# MCU063B_GPIO.net
KiCad netlist of a schematic drawn in Altium Designer
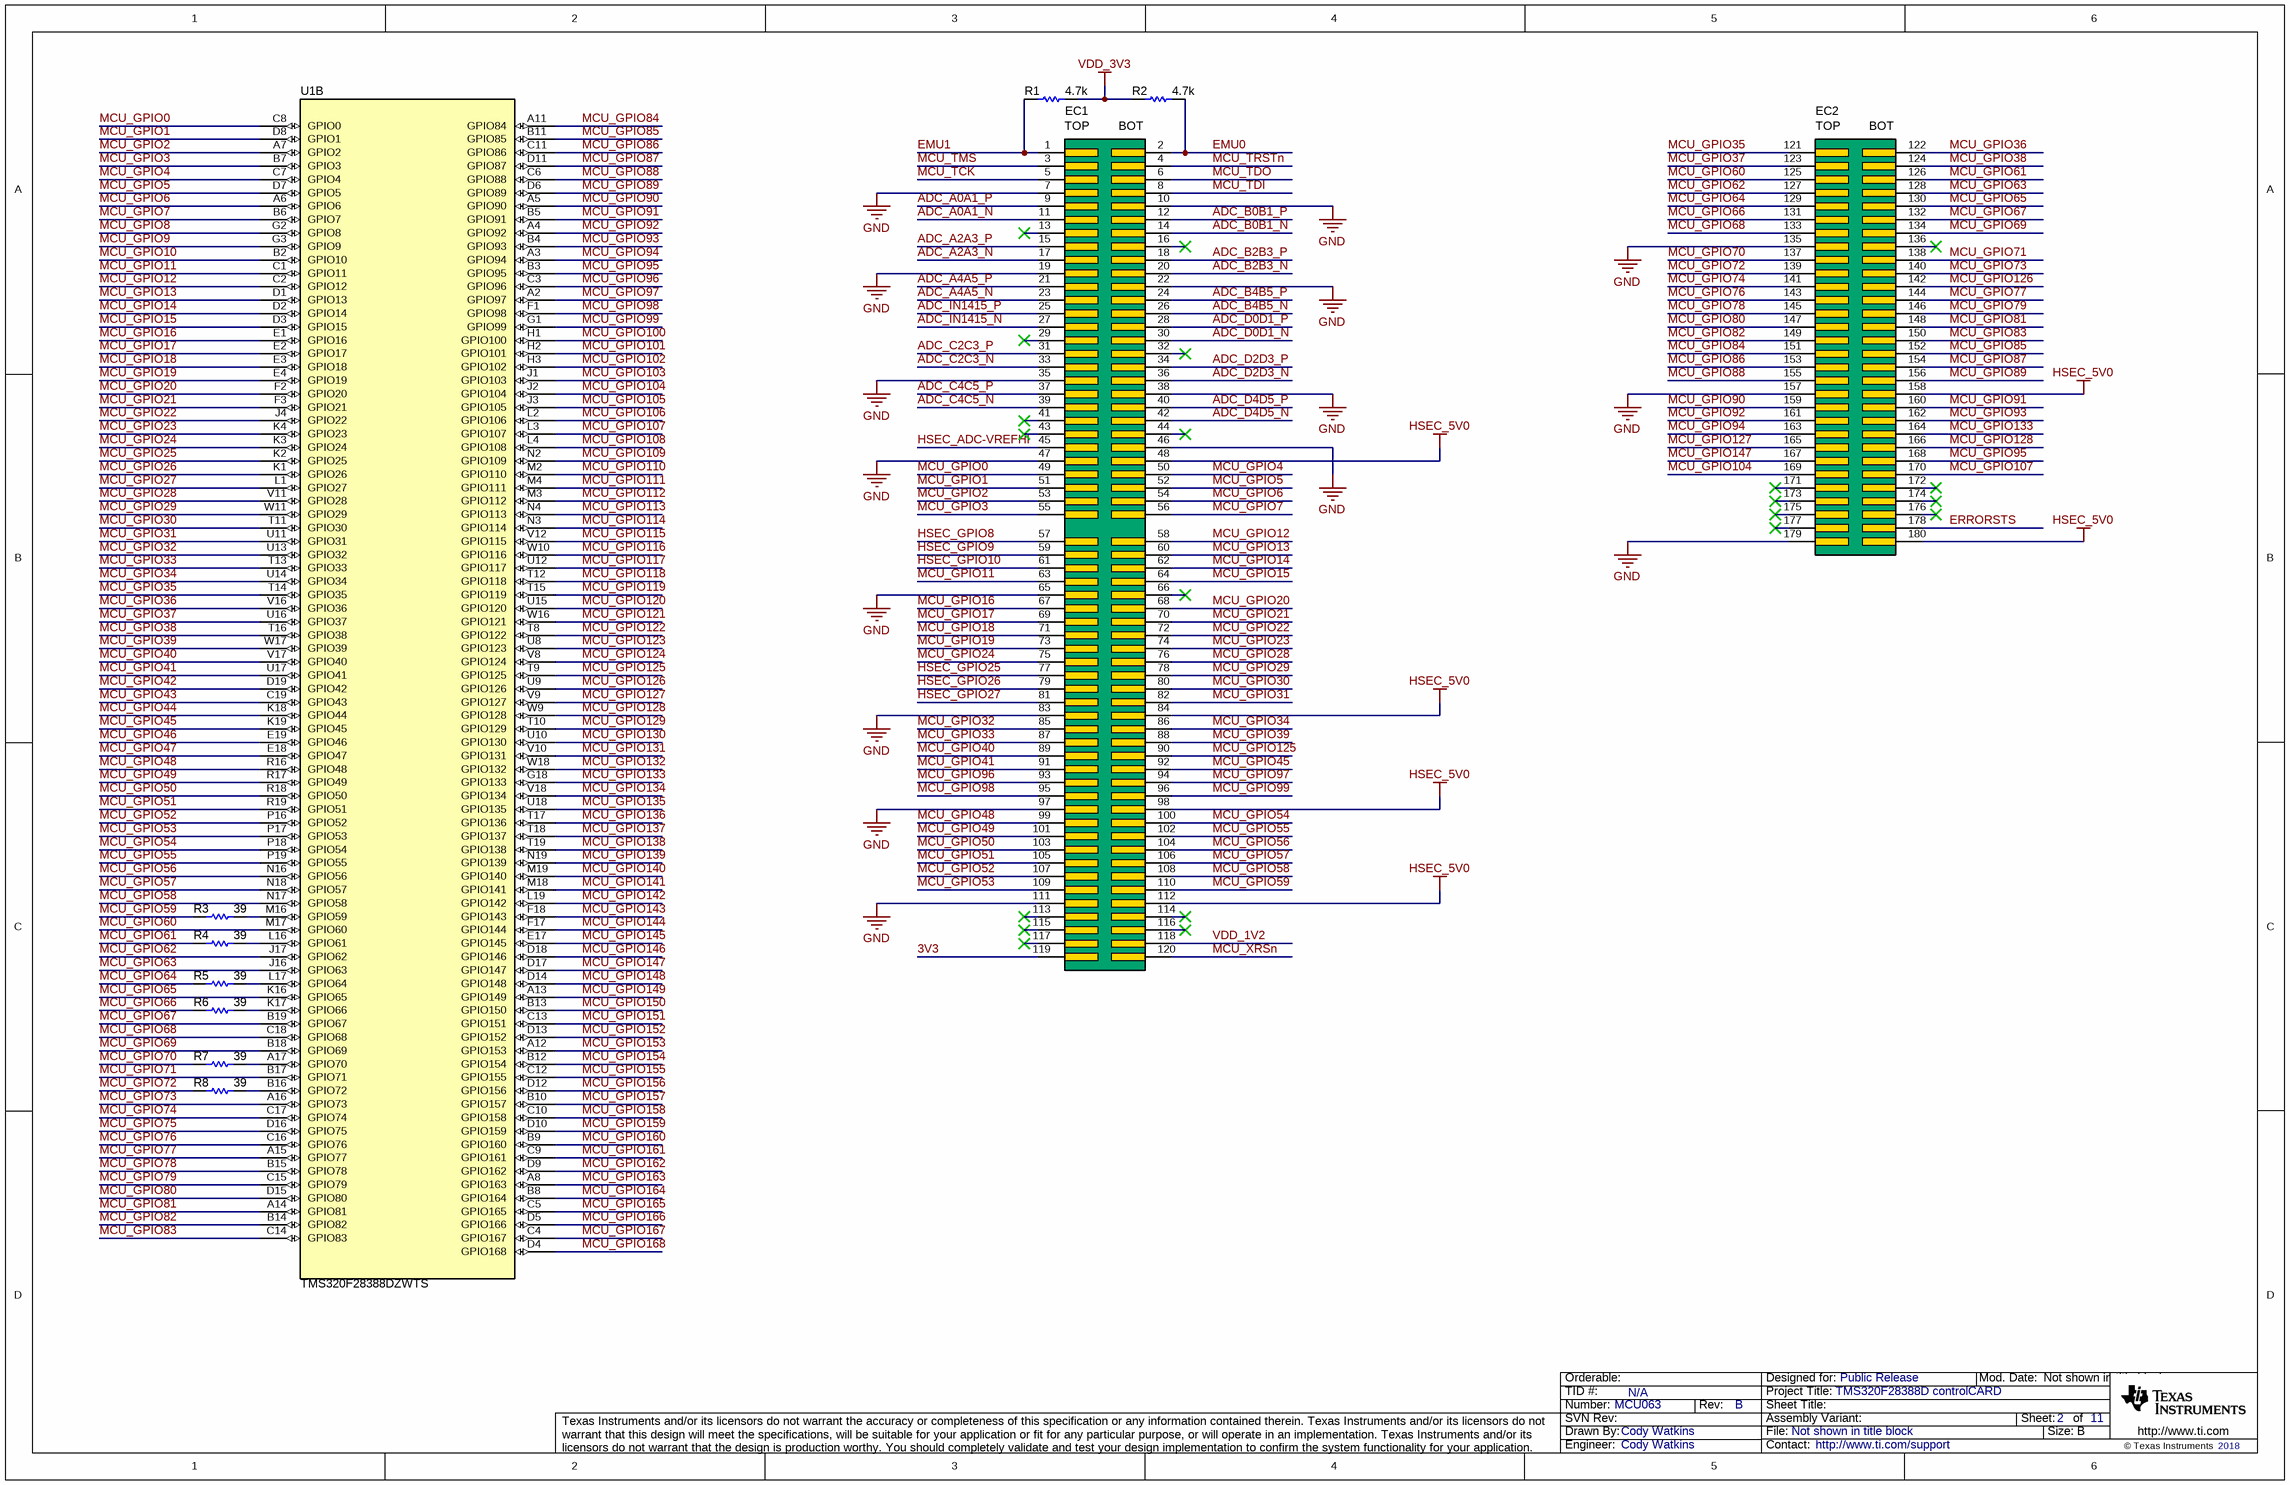
[diagram p0: MCU063B_GPIO.SchDoc]

(export (version "E")
  (design (tool "Eeschema 10.0.6"))
  (components
    (comp (ref "EC1")
      (value "controlCARD-120HSEC_Edge")
      (footprint "controlCARD-120HSEC_Edge")
      (description "C2000 controlCARD-120HSEC Edge Connector for Samtec HSEC8-160-01-L-DV-A-BL")
      (fields (field (name "MANUFACTURER") "Any"))
      (libsource (lib "Altium Vault - TI") (part "controlCARD-120HSEC_Edge"))
    )
    (comp (ref "EC2")
      (value "controlCARD-180HSEC-60pinAddon_Edge")
      (footprint "controlCARD-180HSEC-60pinAddon_Edge")
      (description "C2000 controlCARD-180HSEC (60-pin addon) Edge connector for Samtec HSEC8-130-01-L-DV-A")
      (fields (field (name "MANUFACTURER") "Any"))
      (libsource (lib "Altium Vault - TI") (part "controlCARD-180HSEC-60pinAddon_Edge"))
    )
    (comp (ref "R1")
      (value "CRCW04024K70JNED")
      (footprint "0402")
      (description "RES, 4.7 k, 5%, 0.063 W, AEC-Q200 Grade 0, 0402")
      (fields (field (name "MANUFACTURER") "Vishay-Dale") (field (name "VALUEDISPLAYED") "4.7k"))
      (libsource (lib "Altium Vault - TI") (part "Resistor"))
    )
    (comp (ref "R2")
      (value "CRCW04024K70JNED")
      (footprint "0402")
      (description "RES, 4.7 k, 5%, 0.063 W, AEC-Q200 Grade 0, 0402")
      (fields (field (name "MANUFACTURER") "Vishay-Dale") (field (name "VALUEDISPLAYED") "4.7k"))
      (libsource (lib "Altium Vault - TI") (part "Resistor"))
    )
    (comp (ref "R3")
      (value "CRCW040239R0JNED")
      (footprint "0402")
      (description "RES, 39, 5%, 0.063 W, AEC-Q200 Grade 0, 0402")
      (fields (field (name "MANUFACTURER") "Vishay-Dale") (field (name "VALUEDISPLAYED") "39"))
      (libsource (lib "Altium Vault - TI") (part "Resistor"))
    )
    (comp (ref "R4")
      (value "CRCW040239R0JNED")
      (footprint "0402")
      (description "RES, 39, 5%, 0.063 W, AEC-Q200 Grade 0, 0402")
      (fields (field (name "MANUFACTURER") "Vishay-Dale") (field (name "VALUEDISPLAYED") "39"))
      (libsource (lib "Altium Vault - TI") (part "Resistor"))
    )
    (comp (ref "R5")
      (value "CRCW040239R0JNED")
      (footprint "0402")
      (description "RES, 39, 5%, 0.063 W, AEC-Q200 Grade 0, 0402")
      (fields (field (name "MANUFACTURER") "Vishay-Dale") (field (name "VALUEDISPLAYED") "39"))
      (libsource (lib "Altium Vault - TI") (part "Resistor"))
    )
    (comp (ref "R6")
      (value "CRCW040239R0JNED")
      (footprint "0402")
      (description "RES, 39, 5%, 0.063 W, AEC-Q200 Grade 0, 0402")
      (fields (field (name "MANUFACTURER") "Vishay-Dale") (field (name "VALUEDISPLAYED") "39"))
      (libsource (lib "Altium Vault - TI") (part "Resistor"))
    )
    (comp (ref "R7")
      (value "CRCW040239R0JNED")
      (footprint "0402")
      (description "RES, 39, 5%, 0.063 W, AEC-Q200 Grade 0, 0402")
      (fields (field (name "MANUFACTURER") "Vishay-Dale") (field (name "VALUEDISPLAYED") "39"))
      (libsource (lib "Altium Vault - TI") (part "Resistor"))
    )
    (comp (ref "R8")
      (value "CRCW040239R0JNED")
      (footprint "0402")
      (description "RES, 39, 5%, 0.063 W, AEC-Q200 Grade 0, 0402")
      (fields (field (name "MANUFACTURER") "Vishay-Dale") (field (name "VALUEDISPLAYED") "39"))
      (libsource (lib "Altium Vault - TI") (part "Resistor"))
    )
    (comp (ref "U1")
      (value "TMS320F28388DZWTS")
      (footprint "ZWT0337A")
      (description "TMS320F28388DZWTS, ZWT0337A (NFBGA-337)")
      (fields
        (field (name "PARTNUMBER") "TMS320F28388DZWTS")
        (field (name "MANUFACTURER") "Texas Instruments")
      )
      (libsource (lib "Altium Vault - TI") (part "TMS320F28388"))
    )
  )
  (nets
    (net (code "1") (name "/3V3") (class "Default")
      (node (ref "EC1") (pin "119") (pinfunction "119_119") (pintype "passive"))
    )
    (net (code "2") (name "/ADC_A0A1_N") (class "Default")
      (node (ref "EC1") (pin "11") (pinfunction "11_11") (pintype "passive"))
    )
    (net (code "3") (name "/ADC_A0A1_P") (class "Default")
      (node (ref "EC1") (pin "9") (pinfunction "9_9") (pintype "passive"))
    )
    (net (code "4") (name "/ADC_A2A3_N") (class "Default")
      (node (ref "EC1") (pin "17") (pinfunction "17_17") (pintype "passive"))
    )
    (net (code "5") (name "/ADC_A2A3_P") (class "Default")
      (node (ref "EC1") (pin "15") (pinfunction "15_15") (pintype "passive"))
    )
    (net (code "6") (name "/ADC_A4A5_N") (class "Default")
      (node (ref "EC1") (pin "23") (pinfunction "23_23") (pintype "passive"))
    )
    (net (code "7") (name "/ADC_A4A5_P") (class "Default")
      (node (ref "EC1") (pin "21") (pinfunction "21_21") (pintype "passive"))
    )
    (net (code "8") (name "/ADC_B0B1_N") (class "Default")
      (node (ref "EC1") (pin "14") (pinfunction "14_14") (pintype "passive"))
    )
    (net (code "9") (name "/ADC_B0B1_P") (class "Default")
      (node (ref "EC1") (pin "12") (pinfunction "12_12") (pintype "passive"))
    )
    (net (code "10") (name "/ADC_B2B3_N") (class "Default")
      (node (ref "EC1") (pin "20") (pinfunction "20_20") (pintype "passive"))
    )
    (net (code "11") (name "/ADC_B2B3_P") (class "Default")
      (node (ref "EC1") (pin "18") (pinfunction "18_18") (pintype "passive"))
    )
    (net (code "12") (name "/ADC_B4B5_N") (class "Default")
      (node (ref "EC1") (pin "26") (pinfunction "26_26") (pintype "passive"))
    )
    (net (code "13") (name "/ADC_B4B5_P") (class "Default")
      (node (ref "EC1") (pin "24") (pinfunction "24_24") (pintype "passive"))
    )
    (net (code "14") (name "/ADC_C2C3_N") (class "Default")
      (node (ref "EC1") (pin "33") (pinfunction "33_33") (pintype "passive"))
    )
    (net (code "15") (name "/ADC_C2C3_P") (class "Default")
      (node (ref "EC1") (pin "31") (pinfunction "31_31") (pintype "passive"))
    )
    (net (code "16") (name "/ADC_C4C5_N") (class "Default")
      (node (ref "EC1") (pin "39") (pinfunction "39_39") (pintype "passive"))
    )
    (net (code "17") (name "/ADC_C4C5_P") (class "Default")
      (node (ref "EC1") (pin "37") (pinfunction "37_37") (pintype "passive"))
    )
    (net (code "18") (name "/ADC_D0D1_N") (class "Default")
      (node (ref "EC1") (pin "30") (pinfunction "30_30") (pintype "passive"))
    )
    (net (code "19") (name "/ADC_D0D1_P") (class "Default")
      (node (ref "EC1") (pin "28") (pinfunction "28_28") (pintype "passive"))
    )
    (net (code "20") (name "/ADC_D2D3_N") (class "Default")
      (node (ref "EC1") (pin "36") (pinfunction "36_36") (pintype "passive"))
    )
    (net (code "21") (name "/ADC_D2D3_P") (class "Default")
      (node (ref "EC1") (pin "34") (pinfunction "34_34") (pintype "passive"))
    )
    (net (code "22") (name "/ADC_D4D5_N") (class "Default")
      (node (ref "EC1") (pin "42") (pinfunction "42_42") (pintype "passive"))
    )
    (net (code "23") (name "/ADC_D4D5_P") (class "Default")
      (node (ref "EC1") (pin "40") (pinfunction "40_40") (pintype "passive"))
    )
    (net (code "24") (name "/ADC_IN1415_N") (class "Default")
      (node (ref "EC1") (pin "27") (pinfunction "27_27") (pintype "passive"))
    )
    (net (code "25") (name "/ADC_IN1415_P") (class "Default")
      (node (ref "EC1") (pin "25") (pinfunction "25_25") (pintype "passive"))
    )
    (net (code "26") (name "/EMU0") (class "Default")
      (node (ref "EC1") (pin "2") (pinfunction "2_2") (pintype "passive"))
      (node (ref "R2") (pin "2") (pinfunction "2_2") (pintype "passive"))
    )
    (net (code "27") (name "/EMU1") (class "Default")
      (node (ref "EC1") (pin "1") (pinfunction "1_1") (pintype "passive"))
      (node (ref "R1") (pin "1") (pinfunction "1_1") (pintype "passive"))
    )
    (net (code "28") (name "/ERRORSTS") (class "Default")
      (node (ref "EC2") (pin "178") (pinfunction "178_178") (pintype "passive"))
    )
    (net (code "29") (name "/HSEC_ADC-VREFHI") (class "Default")
      (node (ref "EC1") (pin "45") (pinfunction "45_45") (pintype "passive"))
    )
    (net (code "30") (name "/HSEC_GPIO8") (class "Default")
      (node (ref "EC1") (pin "57") (pinfunction "57_57") (pintype "passive"))
    )
    (net (code "31") (name "/HSEC_GPIO9") (class "Default")
      (node (ref "EC1") (pin "59") (pinfunction "59_59") (pintype "passive"))
    )
    (net (code "32") (name "/HSEC_GPIO10") (class "Default")
      (node (ref "EC1") (pin "61") (pinfunction "61_61") (pintype "passive"))
    )
    (net (code "33") (name "/HSEC_GPIO25") (class "Default")
      (node (ref "EC1") (pin "77") (pinfunction "77_77") (pintype "passive"))
    )
    (net (code "34") (name "/HSEC_GPIO26") (class "Default")
      (node (ref "EC1") (pin "79") (pinfunction "79_79") (pintype "passive"))
    )
    (net (code "35") (name "/HSEC_GPIO27") (class "Default")
      (node (ref "EC1") (pin "81") (pinfunction "81_81") (pintype "passive"))
    )
    (net (code "36") (name "/MCU_GPIO0") (class "Default")
      (node (ref "EC1") (pin "49") (pinfunction "49_49") (pintype "passive"))
      (node (ref "U1") (pin "C8") (pinfunction "GPIO0_C8") (pintype "bidirectional"))
    )
    (net (code "37") (name "/MCU_GPIO1") (class "Default")
      (node (ref "EC1") (pin "51") (pinfunction "51_51") (pintype "passive"))
      (node (ref "U1") (pin "D8") (pinfunction "GPIO1_D8") (pintype "bidirectional"))
    )
    (net (code "38") (name "/MCU_GPIO2") (class "Default")
      (node (ref "EC1") (pin "53") (pinfunction "53_53") (pintype "passive"))
      (node (ref "U1") (pin "A7") (pinfunction "GPIO2_A7") (pintype "bidirectional"))
    )
    (net (code "39") (name "/MCU_GPIO3") (class "Default")
      (node (ref "EC1") (pin "55") (pinfunction "55_55") (pintype "passive"))
      (node (ref "U1") (pin "B7") (pinfunction "GPIO3_B7") (pintype "bidirectional"))
    )
    (net (code "40") (name "/MCU_GPIO4") (class "Default")
      (node (ref "EC1") (pin "50") (pinfunction "50_50") (pintype "passive"))
      (node (ref "U1") (pin "C7") (pinfunction "GPIO4_C7") (pintype "bidirectional"))
    )
    (net (code "41") (name "/MCU_GPIO5") (class "Default")
      (node (ref "EC1") (pin "52") (pinfunction "52_52") (pintype "passive"))
      (node (ref "U1") (pin "D7") (pinfunction "GPIO5_D7") (pintype "bidirectional"))
    )
    (net (code "42") (name "/MCU_GPIO6") (class "Default")
      (node (ref "EC1") (pin "54") (pinfunction "54_54") (pintype "passive"))
      (node (ref "U1") (pin "A6") (pinfunction "GPIO6_A6") (pintype "bidirectional"))
    )
    (net (code "43") (name "/MCU_GPIO7") (class "Default")
      (node (ref "EC1") (pin "56") (pinfunction "56_56") (pintype "passive"))
      (node (ref "U1") (pin "B6") (pinfunction "GPIO7_B6") (pintype "bidirectional"))
    )
    (net (code "44") (name "/MCU_GPIO8") (class "Default")
      (node (ref "U1") (pin "G2") (pinfunction "GPIO8_G2") (pintype "bidirectional"))
    )
    (net (code "45") (name "/MCU_GPIO9") (class "Default")
      (node (ref "U1") (pin "G3") (pinfunction "GPIO9_G3") (pintype "bidirectional"))
    )
    (net (code "46") (name "/MCU_GPIO10") (class "Default")
      (node (ref "U1") (pin "B2") (pinfunction "GPIO10_B2") (pintype "bidirectional"))
    )
    (net (code "47") (name "/MCU_GPIO11") (class "Default")
      (node (ref "EC1") (pin "63") (pinfunction "63_63") (pintype "passive"))
      (node (ref "U1") (pin "C1") (pinfunction "GPIO11_C1") (pintype "bidirectional"))
    )
    (net (code "48") (name "/MCU_GPIO12") (class "Default")
      (node (ref "EC1") (pin "58") (pinfunction "58_58") (pintype "passive"))
      (node (ref "U1") (pin "C2") (pinfunction "GPIO12_C2") (pintype "bidirectional"))
    )
    (net (code "49") (name "/MCU_GPIO13") (class "Default")
      (node (ref "EC1") (pin "60") (pinfunction "60_60") (pintype "passive"))
      (node (ref "U1") (pin "D1") (pinfunction "GPIO13_D1") (pintype "bidirectional"))
    )
    (net (code "50") (name "/MCU_GPIO14") (class "Default")
      (node (ref "EC1") (pin "62") (pinfunction "62_62") (pintype "passive"))
      (node (ref "U1") (pin "D2") (pinfunction "GPIO14_D2") (pintype "bidirectional"))
    )
    (net (code "51") (name "/MCU_GPIO15") (class "Default")
      (node (ref "EC1") (pin "64") (pinfunction "64_64") (pintype "passive"))
      (node (ref "U1") (pin "D3") (pinfunction "GPIO15_D3") (pintype "bidirectional"))
    )
    (net (code "52") (name "/MCU_GPIO16") (class "Default")
      (node (ref "EC1") (pin "67") (pinfunction "67_67") (pintype "passive"))
      (node (ref "U1") (pin "E1") (pinfunction "GPIO16_E1") (pintype "bidirectional"))
    )
    (net (code "53") (name "/MCU_GPIO17") (class "Default")
      (node (ref "EC1") (pin "69") (pinfunction "69_69") (pintype "passive"))
      (node (ref "U1") (pin "E2") (pinfunction "GPIO17_E2") (pintype "bidirectional"))
    )
    (net (code "54") (name "/MCU_GPIO18") (class "Default")
      (node (ref "EC1") (pin "71") (pinfunction "71_71") (pintype "passive"))
      (node (ref "U1") (pin "E3") (pinfunction "GPIO18_E3") (pintype "bidirectional"))
    )
    (net (code "55") (name "/MCU_GPIO19") (class "Default")
      (node (ref "EC1") (pin "73") (pinfunction "73_73") (pintype "passive"))
      (node (ref "U1") (pin "E4") (pinfunction "GPIO19_E4") (pintype "bidirectional"))
    )
    (net (code "56") (name "/MCU_GPIO20") (class "Default")
      (node (ref "EC1") (pin "68") (pinfunction "68_68") (pintype "passive"))
      (node (ref "U1") (pin "F2") (pinfunction "GPIO20_F2") (pintype "bidirectional"))
    )
    (net (code "57") (name "/MCU_GPIO21") (class "Default")
      (node (ref "EC1") (pin "70") (pinfunction "70_70") (pintype "passive"))
      (node (ref "U1") (pin "F3") (pinfunction "GPIO21_F3") (pintype "bidirectional"))
    )
    (net (code "58") (name "/MCU_GPIO22") (class "Default")
      (node (ref "EC1") (pin "72") (pinfunction "72_72") (pintype "passive"))
      (node (ref "U1") (pin "J4") (pinfunction "GPIO22_J4") (pintype "bidirectional"))
    )
    (net (code "59") (name "/MCU_GPIO23") (class "Default")
      (node (ref "EC1") (pin "74") (pinfunction "74_74") (pintype "passive"))
      (node (ref "U1") (pin "K4") (pinfunction "GPIO23_K4") (pintype "bidirectional"))
    )
    (net (code "60") (name "/MCU_GPIO24") (class "Default")
      (node (ref "EC1") (pin "75") (pinfunction "75_75") (pintype "passive"))
      (node (ref "U1") (pin "K3") (pinfunction "GPIO24_K3") (pintype "bidirectional"))
    )
    (net (code "61") (name "/MCU_GPIO25") (class "Default")
      (node (ref "U1") (pin "K2") (pinfunction "GPIO25_K2") (pintype "bidirectional"))
    )
    (net (code "62") (name "/MCU_GPIO26") (class "Default")
      (node (ref "U1") (pin "K1") (pinfunction "GPIO26_K1") (pintype "bidirectional"))
    )
    (net (code "63") (name "/MCU_GPIO27") (class "Default")
      (node (ref "U1") (pin "L1") (pinfunction "GPIO27_L1") (pintype "bidirectional"))
    )
    (net (code "64") (name "/MCU_GPIO28") (class "Default")
      (node (ref "EC1") (pin "76") (pinfunction "76_76") (pintype "passive"))
      (node (ref "U1") (pin "V11") (pinfunction "GPIO28_V11") (pintype "bidirectional"))
    )
    (net (code "65") (name "/MCU_GPIO29") (class "Default")
      (node (ref "EC1") (pin "78") (pinfunction "78_78") (pintype "passive"))
      (node (ref "U1") (pin "W11") (pinfunction "GPIO29_W11") (pintype "bidirectional"))
    )
    (net (code "66") (name "/MCU_GPIO30") (class "Default")
      (node (ref "EC1") (pin "80") (pinfunction "80_80") (pintype "passive"))
      (node (ref "U1") (pin "T11") (pinfunction "GPIO30_T11") (pintype "bidirectional"))
    )
    (net (code "67") (name "/MCU_GPIO31") (class "Default")
      (node (ref "EC1") (pin "82") (pinfunction "82_82") (pintype "passive"))
      (node (ref "U1") (pin "U11") (pinfunction "GPIO31_U11") (pintype "bidirectional"))
    )
    (net (code "68") (name "/MCU_GPIO32") (class "Default")
      (node (ref "EC1") (pin "85") (pinfunction "85_85") (pintype "passive"))
      (node (ref "U1") (pin "U13") (pinfunction "GPIO32_U13") (pintype "bidirectional"))
    )
    (net (code "69") (name "/MCU_GPIO33") (class "Default")
      (node (ref "EC1") (pin "87") (pinfunction "87_87") (pintype "passive"))
      (node (ref "U1") (pin "T13") (pinfunction "GPIO33_T13") (pintype "bidirectional"))
    )
    (net (code "70") (name "/MCU_GPIO34") (class "Default")
      (node (ref "EC1") (pin "86") (pinfunction "86_86") (pintype "passive"))
      (node (ref "U1") (pin "U14") (pinfunction "GPIO34_U14") (pintype "bidirectional"))
    )
    (net (code "71") (name "/MCU_GPIO35") (class "Default")
      (node (ref "EC2") (pin "121") (pinfunction "121_121") (pintype "passive"))
      (node (ref "U1") (pin "T14") (pinfunction "GPIO35_T14") (pintype "bidirectional"))
    )
    (net (code "72") (name "/MCU_GPIO36") (class "Default")
      (node (ref "EC2") (pin "122") (pinfunction "122_122") (pintype "passive"))
      (node (ref "U1") (pin "V16") (pinfunction "GPIO36_V16") (pintype "bidirectional"))
    )
    (net (code "73") (name "/MCU_GPIO37") (class "Default")
      (node (ref "EC2") (pin "123") (pinfunction "123_123") (pintype "passive"))
      (node (ref "U1") (pin "U16") (pinfunction "GPIO37_U16") (pintype "bidirectional"))
    )
    (net (code "74") (name "/MCU_GPIO38") (class "Default")
      (node (ref "EC2") (pin "124") (pinfunction "124_124") (pintype "passive"))
      (node (ref "U1") (pin "T16") (pinfunction "GPIO38_T16") (pintype "bidirectional"))
    )
    (net (code "75") (name "/MCU_GPIO39") (class "Default")
      (node (ref "EC1") (pin "88") (pinfunction "88_88") (pintype "passive"))
      (node (ref "U1") (pin "W17") (pinfunction "GPIO39_W17") (pintype "bidirectional"))
    )
    (net (code "76") (name "/MCU_GPIO40") (class "Default")
      (node (ref "EC1") (pin "89") (pinfunction "89_89") (pintype "passive"))
      (node (ref "U1") (pin "V17") (pinfunction "GPIO40_V17") (pintype "bidirectional"))
    )
    (net (code "77") (name "/MCU_GPIO41") (class "Default")
      (node (ref "EC1") (pin "91") (pinfunction "91_91") (pintype "passive"))
      (node (ref "U1") (pin "U17") (pinfunction "GPIO41_U17") (pintype "bidirectional"))
    )
    (net (code "78") (name "/MCU_GPIO42") (class "Default")
      (node (ref "U1") (pin "D19") (pinfunction "GPIO42_D19") (pintype "bidirectional"))
    )
    (net (code "79") (name "/MCU_GPIO43") (class "Default")
      (node (ref "U1") (pin "C19") (pinfunction "GPIO43_C19") (pintype "bidirectional"))
    )
    (net (code "80") (name "/MCU_GPIO44") (class "Default")
      (node (ref "U1") (pin "K18") (pinfunction "GPIO44_K18") (pintype "bidirectional"))
    )
    (net (code "81") (name "/MCU_GPIO45") (class "Default")
      (node (ref "EC1") (pin "92") (pinfunction "92_92") (pintype "passive"))
      (node (ref "U1") (pin "K19") (pinfunction "GPIO45_K19") (pintype "bidirectional"))
    )
    (net (code "82") (name "/MCU_GPIO46") (class "Default")
      (node (ref "U1") (pin "E19") (pinfunction "GPIO46_E19") (pintype "bidirectional"))
    )
    (net (code "83") (name "/MCU_GPIO47") (class "Default")
      (node (ref "U1") (pin "E18") (pinfunction "GPIO47_E18") (pintype "bidirectional"))
    )
    (net (code "84") (name "/MCU_GPIO48") (class "Default")
      (node (ref "EC1") (pin "99") (pinfunction "99_99") (pintype "passive"))
      (node (ref "U1") (pin "R16") (pinfunction "GPIO48_R16") (pintype "bidirectional"))
    )
    (net (code "85") (name "/MCU_GPIO49") (class "Default")
      (node (ref "EC1") (pin "101") (pinfunction "101_101") (pintype "passive"))
      (node (ref "U1") (pin "R17") (pinfunction "GPIO49_R17") (pintype "bidirectional"))
    )
    (net (code "86") (name "/MCU_GPIO50") (class "Default")
      (node (ref "EC1") (pin "103") (pinfunction "103_103") (pintype "passive"))
      (node (ref "U1") (pin "R18") (pinfunction "GPIO50_R18") (pintype "bidirectional"))
    )
    (net (code "87") (name "/MCU_GPIO51") (class "Default")
      (node (ref "EC1") (pin "105") (pinfunction "105_105") (pintype "passive"))
      (node (ref "U1") (pin "R19") (pinfunction "GPIO51_R19") (pintype "bidirectional"))
    )
    (net (code "88") (name "/MCU_GPIO52") (class "Default")
      (node (ref "EC1") (pin "107") (pinfunction "107_107") (pintype "passive"))
      (node (ref "U1") (pin "P16") (pinfunction "GPIO52_P16") (pintype "bidirectional"))
    )
    (net (code "89") (name "/MCU_GPIO53") (class "Default")
      (node (ref "EC1") (pin "109") (pinfunction "109_109") (pintype "passive"))
      (node (ref "U1") (pin "P17") (pinfunction "GPIO53_P17") (pintype "bidirectional"))
    )
    (net (code "90") (name "/MCU_GPIO54") (class "Default")
      (node (ref "EC1") (pin "100") (pinfunction "100_100") (pintype "passive"))
      (node (ref "U1") (pin "P18") (pinfunction "GPIO54_P18") (pintype "bidirectional"))
    )
    (net (code "91") (name "/MCU_GPIO55") (class "Default")
      (node (ref "EC1") (pin "102") (pinfunction "102_102") (pintype "passive"))
      (node (ref "U1") (pin "P19") (pinfunction "GPIO55_P19") (pintype "bidirectional"))
    )
    (net (code "92") (name "/MCU_GPIO56") (class "Default")
      (node (ref "EC1") (pin "104") (pinfunction "104_104") (pintype "passive"))
      (node (ref "U1") (pin "N16") (pinfunction "GPIO56_N16") (pintype "bidirectional"))
    )
    (net (code "93") (name "/MCU_GPIO57") (class "Default")
      (node (ref "EC1") (pin "106") (pinfunction "106_106") (pintype "passive"))
      (node (ref "U1") (pin "N18") (pinfunction "GPIO57_N18") (pintype "bidirectional"))
    )
    (net (code "94") (name "/MCU_GPIO58") (class "Default")
      (node (ref "EC1") (pin "108") (pinfunction "108_108") (pintype "passive"))
      (node (ref "U1") (pin "N17") (pinfunction "GPIO58_N17") (pintype "bidirectional"))
    )
    (net (code "95") (name "/MCU_GPIO59") (class "Default")
      (node (ref "EC1") (pin "110") (pinfunction "110_110") (pintype "passive"))
      (node (ref "R3") (pin "1") (pinfunction "1_1") (pintype "passive"))
    )
    (net (code "96") (name "/MCU_GPIO60") (class "Default")
      (node (ref "EC2") (pin "125") (pinfunction "125_125") (pintype "passive"))
      (node (ref "U1") (pin "M17") (pinfunction "GPIO60_M17") (pintype "bidirectional"))
    )
    (net (code "97") (name "/MCU_GPIO61") (class "Default")
      (node (ref "EC2") (pin "126") (pinfunction "126_126") (pintype "passive"))
      (node (ref "R4") (pin "1") (pinfunction "1_1") (pintype "passive"))
    )
    (net (code "98") (name "/MCU_GPIO62") (class "Default")
      (node (ref "EC2") (pin "127") (pinfunction "127_127") (pintype "passive"))
      (node (ref "U1") (pin "J17") (pinfunction "GPIO62_J17") (pintype "bidirectional"))
    )
    (net (code "99") (name "/MCU_GPIO63") (class "Default")
      (node (ref "EC2") (pin "128") (pinfunction "128_128") (pintype "passive"))
      (node (ref "U1") (pin "J16") (pinfunction "GPIO63_J16") (pintype "bidirectional"))
    )
    (net (code "100") (name "/MCU_GPIO64") (class "Default")
      (node (ref "EC2") (pin "129") (pinfunction "129_129") (pintype "passive"))
      (node (ref "R5") (pin "1") (pinfunction "1_1") (pintype "passive"))
    )
    (net (code "101") (name "/MCU_GPIO65") (class "Default")
      (node (ref "EC2") (pin "130") (pinfunction "130_130") (pintype "passive"))
      (node (ref "U1") (pin "K16") (pinfunction "GPIO65_K16") (pintype "bidirectional"))
    )
    (net (code "102") (name "/MCU_GPIO66") (class "Default")
      (node (ref "EC2") (pin "131") (pinfunction "131_131") (pintype "passive"))
      (node (ref "R6") (pin "1") (pinfunction "1_1") (pintype "passive"))
    )
    (net (code "103") (name "/MCU_GPIO67") (class "Default")
      (node (ref "EC2") (pin "132") (pinfunction "132_132") (pintype "passive"))
      (node (ref "U1") (pin "B19") (pinfunction "GPIO67_B19") (pintype "bidirectional"))
    )
    (net (code "104") (name "/MCU_GPIO68") (class "Default")
      (node (ref "EC2") (pin "133") (pinfunction "133_133") (pintype "passive"))
      (node (ref "U1") (pin "C18") (pinfunction "GPIO68_C18") (pintype "bidirectional"))
    )
    (net (code "105") (name "/MCU_GPIO69") (class "Default")
      (node (ref "EC2") (pin "134") (pinfunction "134_134") (pintype "passive"))
      (node (ref "U1") (pin "B18") (pinfunction "GPIO69_B18") (pintype "bidirectional"))
    )
    (net (code "106") (name "/MCU_GPIO70") (class "Default")
      (node (ref "EC2") (pin "137") (pinfunction "137_137") (pintype "passive"))
      (node (ref "R7") (pin "1") (pinfunction "1_1") (pintype "passive"))
    )
    (net (code "107") (name "/MCU_GPIO71") (class "Default")
      (node (ref "EC2") (pin "138") (pinfunction "138_138") (pintype "passive"))
      (node (ref "U1") (pin "B17") (pinfunction "GPIO71_B17") (pintype "bidirectional"))
    )
    (net (code "108") (name "/MCU_GPIO72") (class "Default")
      (node (ref "EC2") (pin "139") (pinfunction "139_139") (pintype "passive"))
      (node (ref "R8") (pin "1") (pinfunction "1_1") (pintype "passive"))
    )
    (net (code "109") (name "/MCU_GPIO73") (class "Default")
      (node (ref "EC2") (pin "140") (pinfunction "140_140") (pintype "passive"))
      (node (ref "U1") (pin "A16") (pinfunction "GPIO73_A16") (pintype "bidirectional"))
    )
    (net (code "110") (name "/MCU_GPIO74") (class "Default")
      (node (ref "EC2") (pin "141") (pinfunction "141_141") (pintype "passive"))
      (node (ref "U1") (pin "C17") (pinfunction "GPIO74_C17") (pintype "bidirectional"))
    )
    (net (code "111") (name "/MCU_GPIO75") (class "Default")
      (node (ref "U1") (pin "D16") (pinfunction "GPIO75_D16") (pintype "bidirectional"))
    )
    (net (code "112") (name "/MCU_GPIO76") (class "Default")
      (node (ref "EC2") (pin "143") (pinfunction "143_143") (pintype "passive"))
      (node (ref "U1") (pin "C16") (pinfunction "GPIO76_C16") (pintype "bidirectional"))
    )
    (net (code "113") (name "/MCU_GPIO77") (class "Default")
      (node (ref "EC2") (pin "144") (pinfunction "144_144") (pintype "passive"))
      (node (ref "U1") (pin "A15") (pinfunction "GPIO77_A15") (pintype "bidirectional"))
    )
    (net (code "114") (name "/MCU_GPIO78") (class "Default")
      (node (ref "EC2") (pin "145") (pinfunction "145_145") (pintype "passive"))
      (node (ref "U1") (pin "B15") (pinfunction "GPIO78_B15") (pintype "bidirectional"))
    )
    (net (code "115") (name "/MCU_GPIO79") (class "Default")
      (node (ref "EC2") (pin "146") (pinfunction "146_146") (pintype "passive"))
      (node (ref "U1") (pin "C15") (pinfunction "GPIO79_C15") (pintype "bidirectional"))
    )
    (net (code "116") (name "/MCU_GPIO80") (class "Default")
      (node (ref "EC2") (pin "147") (pinfunction "147_147") (pintype "passive"))
      (node (ref "U1") (pin "D15") (pinfunction "GPIO80_D15") (pintype "bidirectional"))
    )
    (net (code "117") (name "/MCU_GPIO81") (class "Default")
      (node (ref "EC2") (pin "148") (pinfunction "148_148") (pintype "passive"))
      (node (ref "U1") (pin "A14") (pinfunction "GPIO81_A14") (pintype "bidirectional"))
    )
    (net (code "118") (name "/MCU_GPIO82") (class "Default")
      (node (ref "EC2") (pin "149") (pinfunction "149_149") (pintype "passive"))
      (node (ref "U1") (pin "B14") (pinfunction "GPIO82_B14") (pintype "bidirectional"))
    )
    (net (code "119") (name "/MCU_GPIO83") (class "Default")
      (node (ref "EC2") (pin "150") (pinfunction "150_150") (pintype "passive"))
      (node (ref "U1") (pin "C14") (pinfunction "GPIO83_C14") (pintype "bidirectional"))
    )
    (net (code "120") (name "/MCU_GPIO84") (class "Default")
      (node (ref "EC2") (pin "151") (pinfunction "151_151") (pintype "passive"))
      (node (ref "U1") (pin "A11") (pinfunction "GPIO84_A11") (pintype "bidirectional"))
    )
    (net (code "121") (name "/MCU_GPIO85") (class "Default")
      (node (ref "EC2") (pin "152") (pinfunction "152_152") (pintype "passive"))
      (node (ref "U1") (pin "B11") (pinfunction "GPIO85_B11") (pintype "bidirectional"))
    )
    (net (code "122") (name "/MCU_GPIO86") (class "Default")
      (node (ref "EC2") (pin "153") (pinfunction "153_153") (pintype "passive"))
      (node (ref "U1") (pin "C11") (pinfunction "GPIO86_C11") (pintype "bidirectional"))
    )
    (net (code "123") (name "/MCU_GPIO87") (class "Default")
      (node (ref "EC2") (pin "154") (pinfunction "154_154") (pintype "passive"))
      (node (ref "U1") (pin "D11") (pinfunction "GPIO87_D11") (pintype "bidirectional"))
    )
    (net (code "124") (name "/MCU_GPIO88") (class "Default")
      (node (ref "EC2") (pin "155") (pinfunction "155_155") (pintype "passive"))
      (node (ref "U1") (pin "C6") (pinfunction "GPIO88_C6") (pintype "bidirectional"))
    )
    (net (code "125") (name "/MCU_GPIO89") (class "Default")
      (node (ref "EC2") (pin "156") (pinfunction "156_156") (pintype "passive"))
      (node (ref "U1") (pin "D6") (pinfunction "GPIO89_D6") (pintype "bidirectional"))
    )
    (net (code "126") (name "/MCU_GPIO90") (class "Default")
      (node (ref "EC2") (pin "159") (pinfunction "159_159") (pintype "passive"))
      (node (ref "U1") (pin "A5") (pinfunction "GPIO90_A5") (pintype "bidirectional"))
    )
    (net (code "127") (name "/MCU_GPIO91") (class "Default")
      (node (ref "EC2") (pin "160") (pinfunction "160_160") (pintype "passive"))
      (node (ref "U1") (pin "B5") (pinfunction "GPIO91_B5") (pintype "bidirectional"))
    )
    (net (code "128") (name "/MCU_GPIO92") (class "Default")
      (node (ref "EC2") (pin "161") (pinfunction "161_161") (pintype "passive"))
      (node (ref "U1") (pin "A4") (pinfunction "GPIO92_A4") (pintype "bidirectional"))
    )
    (net (code "129") (name "/MCU_GPIO93") (class "Default")
      (node (ref "EC2") (pin "162") (pinfunction "162_162") (pintype "passive"))
      (node (ref "U1") (pin "B4") (pinfunction "GPIO93_B4") (pintype "bidirectional"))
    )
    (net (code "130") (name "/MCU_GPIO94") (class "Default")
      (node (ref "EC2") (pin "163") (pinfunction "163_163") (pintype "passive"))
      (node (ref "U1") (pin "A3") (pinfunction "GPIO94_A3") (pintype "bidirectional"))
    )
    (net (code "131") (name "/MCU_GPIO95") (class "Default")
      (node (ref "EC2") (pin "168") (pinfunction "168_168") (pintype "passive"))
      (node (ref "U1") (pin "B3") (pinfunction "GPIO95_B3") (pintype "bidirectional"))
    )
    (net (code "132") (name "/MCU_GPIO96") (class "Default")
      (node (ref "EC1") (pin "93") (pinfunction "93_93") (pintype "passive"))
      (node (ref "U1") (pin "C3") (pinfunction "GPIO96_C3") (pintype "bidirectional"))
    )
    (net (code "133") (name "/MCU_GPIO97") (class "Default")
      (node (ref "EC1") (pin "94") (pinfunction "94_94") (pintype "passive"))
      (node (ref "U1") (pin "A2") (pinfunction "GPIO97_A2") (pintype "bidirectional"))
    )
    (net (code "134") (name "/MCU_GPIO98") (class "Default")
      (node (ref "EC1") (pin "95") (pinfunction "95_95") (pintype "passive"))
      (node (ref "U1") (pin "F1") (pinfunction "GPIO98_F1") (pintype "bidirectional"))
    )
    (net (code "135") (name "/MCU_GPIO99") (class "Default")
      (node (ref "EC1") (pin "96") (pinfunction "96_96") (pintype "passive"))
      (node (ref "U1") (pin "G1") (pinfunction "GPIO99_G1") (pintype "bidirectional"))
    )
    (net (code "136") (name "/MCU_GPIO100") (class "Default")
      (node (ref "U1") (pin "H1") (pinfunction "GPIO100_H1") (pintype "bidirectional"))
    )
    (net (code "137") (name "/MCU_GPIO101") (class "Default")
      (node (ref "U1") (pin "H2") (pinfunction "GPIO101_H2") (pintype "bidirectional"))
    )
    (net (code "138") (name "/MCU_GPIO102") (class "Default")
      (node (ref "U1") (pin "H3") (pinfunction "GPIO102_H3") (pintype "bidirectional"))
    )
    (net (code "139") (name "/MCU_GPIO103") (class "Default")
      (node (ref "U1") (pin "J1") (pinfunction "GPIO103_J1") (pintype "bidirectional"))
    )
    (net (code "140") (name "/MCU_GPIO104") (class "Default")
      (node (ref "EC2") (pin "169") (pinfunction "169_169") (pintype "passive"))
      (node (ref "U1") (pin "J2") (pinfunction "GPIO104_J2") (pintype "bidirectional"))
    )
    (net (code "141") (name "/MCU_GPIO105") (class "Default")
      (node (ref "U1") (pin "J3") (pinfunction "GPIO105_J3") (pintype "bidirectional"))
    )
    (net (code "142") (name "/MCU_GPIO106") (class "Default")
      (node (ref "U1") (pin "L2") (pinfunction "GPIO106_L2") (pintype "bidirectional"))
    )
    (net (code "143") (name "/MCU_GPIO107") (class "Default")
      (node (ref "EC2") (pin "170") (pinfunction "170_170") (pintype "passive"))
      (node (ref "U1") (pin "L3") (pinfunction "GPIO107_L3") (pintype "bidirectional"))
    )
    (net (code "144") (name "/MCU_GPIO108") (class "Default")
      (node (ref "U1") (pin "L4") (pinfunction "GPIO108_L4") (pintype "bidirectional"))
    )
    (net (code "145") (name "/MCU_GPIO109") (class "Default")
      (node (ref "U1") (pin "N2") (pinfunction "GPIO109_N2") (pintype "bidirectional"))
    )
    (net (code "146") (name "/MCU_GPIO110") (class "Default")
      (node (ref "U1") (pin "M2") (pinfunction "GPIO110_M2") (pintype "bidirectional"))
    )
    (net (code "147") (name "/MCU_GPIO111") (class "Default")
      (node (ref "U1") (pin "M4") (pinfunction "GPIO111_M4") (pintype "bidirectional"))
    )
    (net (code "148") (name "/MCU_GPIO112") (class "Default")
      (node (ref "U1") (pin "M3") (pinfunction "GPIO112_M3") (pintype "bidirectional"))
    )
    (net (code "149") (name "/MCU_GPIO113") (class "Default")
      (node (ref "U1") (pin "N4") (pinfunction "GPIO113_N4") (pintype "bidirectional"))
    )
    (net (code "150") (name "/MCU_GPIO114") (class "Default")
      (node (ref "U1") (pin "N3") (pinfunction "GPIO114_N3") (pintype "bidirectional"))
    )
    (net (code "151") (name "/MCU_GPIO115") (class "Default")
      (node (ref "U1") (pin "V12") (pinfunction "GPIO115_V12") (pintype "bidirectional"))
    )
    (net (code "152") (name "/MCU_GPIO116") (class "Default")
      (node (ref "U1") (pin "W10") (pinfunction "GPIO116_W10") (pintype "bidirectional"))
    )
    (net (code "153") (name "/MCU_GPIO117") (class "Default")
      (node (ref "U1") (pin "U12") (pinfunction "GPIO117_U12") (pintype "bidirectional"))
    )
    (net (code "154") (name "/MCU_GPIO118") (class "Default")
      (node (ref "U1") (pin "T12") (pinfunction "GPIO118_T12") (pintype "bidirectional"))
    )
    (net (code "155") (name "/MCU_GPIO119") (class "Default")
      (node (ref "U1") (pin "T15") (pinfunction "GPIO119_T15") (pintype "bidirectional"))
    )
    (net (code "156") (name "/MCU_GPIO120") (class "Default")
      (node (ref "U1") (pin "U15") (pinfunction "GPIO120_U15") (pintype "bidirectional"))
    )
    (net (code "157") (name "/MCU_GPIO121") (class "Default")
      (node (ref "U1") (pin "W16") (pinfunction "GPIO121_W16") (pintype "bidirectional"))
    )
    (net (code "158") (name "/MCU_GPIO122") (class "Default")
      (node (ref "U1") (pin "T8") (pinfunction "GPIO122_T8") (pintype "bidirectional"))
    )
    (net (code "159") (name "/MCU_GPIO123") (class "Default")
      (node (ref "U1") (pin "U8") (pinfunction "GPIO123_U8") (pintype "bidirectional"))
    )
    (net (code "160") (name "/MCU_GPIO124") (class "Default")
      (node (ref "U1") (pin "V8") (pinfunction "GPIO124_V8") (pintype "bidirectional"))
    )
    (net (code "161") (name "/MCU_GPIO125") (class "Default")
      (node (ref "EC1") (pin "90") (pinfunction "90_90") (pintype "passive"))
      (node (ref "U1") (pin "T9") (pinfunction "GPIO125_T9") (pintype "bidirectional"))
    )
    (net (code "162") (name "/MCU_GPIO126") (class "Default")
      (node (ref "EC2") (pin "142") (pinfunction "142_142") (pintype "passive"))
      (node (ref "U1") (pin "U9") (pinfunction "GPIO126_U9") (pintype "bidirectional"))
    )
    (net (code "163") (name "/MCU_GPIO127") (class "Default")
      (node (ref "EC2") (pin "165") (pinfunction "165_165") (pintype "passive"))
      (node (ref "U1") (pin "V9") (pinfunction "GPIO127_V9") (pintype "bidirectional"))
    )
    (net (code "164") (name "/MCU_GPIO128") (class "Default")
      (node (ref "EC2") (pin "166") (pinfunction "166_166") (pintype "passive"))
      (node (ref "U1") (pin "W9") (pinfunction "GPIO128_W9") (pintype "bidirectional"))
    )
    (net (code "165") (name "/MCU_GPIO129") (class "Default")
      (node (ref "U1") (pin "T10") (pinfunction "GPIO129_T10") (pintype "bidirectional"))
    )
    (net (code "166") (name "/MCU_GPIO130") (class "Default")
      (node (ref "U1") (pin "U10") (pinfunction "GPIO130_U10") (pintype "bidirectional"))
    )
    (net (code "167") (name "/MCU_GPIO131") (class "Default")
      (node (ref "U1") (pin "V10") (pinfunction "GPIO131_V10") (pintype "bidirectional"))
    )
    (net (code "168") (name "/MCU_GPIO132") (class "Default")
      (node (ref "U1") (pin "W18") (pinfunction "GPIO132_W18") (pintype "bidirectional"))
    )
    (net (code "169") (name "/MCU_GPIO133") (class "Default")
      (node (ref "EC2") (pin "164") (pinfunction "164_164") (pintype "passive"))
      (node (ref "U1") (pin "G18") (pinfunction "GPIO133_G18") (pintype "bidirectional"))
    )
    (net (code "170") (name "/MCU_GPIO134") (class "Default")
      (node (ref "U1") (pin "V18") (pinfunction "GPIO134_V18") (pintype "bidirectional"))
    )
    (net (code "171") (name "/MCU_GPIO135") (class "Default")
      (node (ref "U1") (pin "U18") (pinfunction "GPIO135_U18") (pintype "bidirectional"))
    )
    (net (code "172") (name "/MCU_GPIO136") (class "Default")
      (node (ref "U1") (pin "T17") (pinfunction "GPIO136_T17") (pintype "bidirectional"))
    )
    (net (code "173") (name "/MCU_GPIO137") (class "Default")
      (node (ref "U1") (pin "T18") (pinfunction "GPIO137_T18") (pintype "bidirectional"))
    )
    (net (code "174") (name "/MCU_GPIO138") (class "Default")
      (node (ref "U1") (pin "T19") (pinfunction "GPIO138_T19") (pintype "bidirectional"))
    )
    (net (code "175") (name "/MCU_GPIO139") (class "Default")
      (node (ref "U1") (pin "N19") (pinfunction "GPIO139_N19") (pintype "bidirectional"))
    )
    (net (code "176") (name "/MCU_GPIO140") (class "Default")
      (node (ref "U1") (pin "M19") (pinfunction "GPIO140_M19") (pintype "bidirectional"))
    )
    (net (code "177") (name "/MCU_GPIO141") (class "Default")
      (node (ref "U1") (pin "M18") (pinfunction "GPIO141_M18") (pintype "bidirectional"))
    )
    (net (code "178") (name "/MCU_GPIO142") (class "Default")
      (node (ref "U1") (pin "L19") (pinfunction "GPIO142_L19") (pintype "bidirectional"))
    )
    (net (code "179") (name "/MCU_GPIO143") (class "Default")
      (node (ref "U1") (pin "F18") (pinfunction "GPIO143_F18") (pintype "bidirectional"))
    )
    (net (code "180") (name "/MCU_GPIO144") (class "Default")
      (node (ref "U1") (pin "F17") (pinfunction "GPIO144_F17") (pintype "bidirectional"))
    )
    (net (code "181") (name "/MCU_GPIO145") (class "Default")
      (node (ref "U1") (pin "E17") (pinfunction "GPIO145_E17") (pintype "bidirectional"))
    )
    (net (code "182") (name "/MCU_GPIO146") (class "Default")
      (node (ref "U1") (pin "D18") (pinfunction "GPIO146_D18") (pintype "bidirectional"))
    )
    (net (code "183") (name "/MCU_GPIO147") (class "Default")
      (node (ref "EC2") (pin "167") (pinfunction "167_167") (pintype "passive"))
      (node (ref "U1") (pin "D17") (pinfunction "GPIO147_D17") (pintype "bidirectional"))
    )
    (net (code "184") (name "/MCU_GPIO148") (class "Default")
      (node (ref "U1") (pin "D14") (pinfunction "GPIO148_D14") (pintype "bidirectional"))
    )
    (net (code "185") (name "/MCU_GPIO149") (class "Default")
      (node (ref "U1") (pin "A13") (pinfunction "GPIO149_A13") (pintype "bidirectional"))
    )
    (net (code "186") (name "/MCU_GPIO150") (class "Default")
      (node (ref "U1") (pin "B13") (pinfunction "GPIO150_B13") (pintype "bidirectional"))
    )
    (net (code "187") (name "/MCU_GPIO151") (class "Default")
      (node (ref "U1") (pin "C13") (pinfunction "GPIO151_C13") (pintype "bidirectional"))
    )
    (net (code "188") (name "/MCU_GPIO152") (class "Default")
      (node (ref "U1") (pin "D13") (pinfunction "GPIO152_D13") (pintype "bidirectional"))
    )
    (net (code "189") (name "/MCU_GPIO153") (class "Default")
      (node (ref "U1") (pin "A12") (pinfunction "GPIO153_A12") (pintype "bidirectional"))
    )
    (net (code "190") (name "/MCU_GPIO154") (class "Default")
      (node (ref "U1") (pin "B12") (pinfunction "GPIO154_B12") (pintype "bidirectional"))
    )
    (net (code "191") (name "/MCU_GPIO155") (class "Default")
      (node (ref "U1") (pin "C12") (pinfunction "GPIO155_C12") (pintype "bidirectional"))
    )
    (net (code "192") (name "/MCU_GPIO156") (class "Default")
      (node (ref "U1") (pin "D12") (pinfunction "GPIO156_D12") (pintype "bidirectional"))
    )
    (net (code "193") (name "/MCU_GPIO157") (class "Default")
      (node (ref "U1") (pin "B10") (pinfunction "GPIO157_B10") (pintype "bidirectional"))
    )
    (net (code "194") (name "/MCU_GPIO158") (class "Default")
      (node (ref "U1") (pin "C10") (pinfunction "GPIO158_C10") (pintype "bidirectional"))
    )
    (net (code "195") (name "/MCU_GPIO159") (class "Default")
      (node (ref "U1") (pin "D10") (pinfunction "GPIO159_D10") (pintype "bidirectional"))
    )
    (net (code "196") (name "/MCU_GPIO160") (class "Default")
      (node (ref "U1") (pin "B9") (pinfunction "GPIO160_B9") (pintype "bidirectional"))
    )
    (net (code "197") (name "/MCU_GPIO161") (class "Default")
      (node (ref "U1") (pin "C9") (pinfunction "GPIO161_C9") (pintype "bidirectional"))
    )
    (net (code "198") (name "/MCU_GPIO162") (class "Default")
      (node (ref "U1") (pin "D9") (pinfunction "GPIO162_D9") (pintype "bidirectional"))
    )
    (net (code "199") (name "/MCU_GPIO163") (class "Default")
      (node (ref "U1") (pin "A8") (pinfunction "GPIO163_A8") (pintype "bidirectional"))
    )
    (net (code "200") (name "/MCU_GPIO164") (class "Default")
      (node (ref "U1") (pin "B8") (pinfunction "GPIO164_B8") (pintype "bidirectional"))
    )
    (net (code "201") (name "/MCU_GPIO165") (class "Default")
      (node (ref "U1") (pin "C5") (pinfunction "GPIO165_C5") (pintype "bidirectional"))
    )
    (net (code "202") (name "/MCU_GPIO166") (class "Default")
      (node (ref "U1") (pin "D5") (pinfunction "GPIO166_D5") (pintype "bidirectional"))
    )
    (net (code "203") (name "/MCU_GPIO167") (class "Default")
      (node (ref "U1") (pin "C4") (pinfunction "GPIO167_C4") (pintype "bidirectional"))
    )
    (net (code "204") (name "/MCU_GPIO168") (class "Default")
      (node (ref "U1") (pin "D4") (pinfunction "GPIO168_D4") (pintype "bidirectional"))
    )
    (net (code "205") (name "/MCU_TCK") (class "Default")
      (node (ref "EC1") (pin "5") (pinfunction "5_5") (pintype "passive"))
    )
    (net (code "206") (name "/MCU_TDI") (class "Default")
      (node (ref "EC1") (pin "8") (pinfunction "8_8") (pintype "passive"))
    )
    (net (code "207") (name "/MCU_TDO") (class "Default")
      (node (ref "EC1") (pin "6") (pinfunction "6_6") (pintype "passive"))
    )
    (net (code "208") (name "/MCU_TMS") (class "Default")
      (node (ref "EC1") (pin "3") (pinfunction "3_3") (pintype "passive"))
    )
    (net (code "209") (name "/MCU_TRSTn") (class "Default")
      (node (ref "EC1") (pin "4") (pinfunction "4_4") (pintype "passive"))
    )
    (net (code "210") (name "/MCU_XRSn") (class "Default")
      (node (ref "EC1") (pin "120") (pinfunction "120_120") (pintype "passive"))
    )
    (net (code "211") (name "/VDD_1V2") (class "Default")
      (node (ref "EC1") (pin "118") (pinfunction "118_118") (pintype "passive"))
    )
    (net (code "212") (name "GND") (class "Default")
      (node (ref "EC1") (pin "10") (pinfunction "10_10") (pintype "passive"))
      (node (ref "EC1") (pin "111") (pinfunction "111_111") (pintype "passive"))
      (node (ref "EC1") (pin "19") (pinfunction "19_19") (pintype "passive"))
      (node (ref "EC1") (pin "22") (pinfunction "22_22") (pintype "passive"))
      (node (ref "EC1") (pin "35") (pinfunction "35_35") (pintype "passive"))
      (node (ref "EC1") (pin "38") (pinfunction "38_38") (pintype "passive"))
      (node (ref "EC1") (pin "46") (pinfunction "46_46") (pintype "passive"))
      (node (ref "EC1") (pin "47") (pinfunction "47_47") (pintype "passive"))
      (node (ref "EC1") (pin "65") (pinfunction "65_65") (pintype "passive"))
      (node (ref "EC1") (pin "7") (pinfunction "7_7") (pintype "passive"))
      (node (ref "EC1") (pin "83") (pinfunction "83_83") (pintype "passive"))
      (node (ref "EC1") (pin "97") (pinfunction "97_97") (pintype "passive"))
      (node (ref "EC2") (pin "135") (pinfunction "135_135") (pintype "passive"))
      (node (ref "EC2") (pin "157") (pinfunction "157_157") (pintype "passive"))
      (node (ref "EC2") (pin "179") (pinfunction "179_179") (pintype "passive"))
    )
    (net (code "213") (name "HSEC_5V0") (class "Default")
      (node (ref "EC1") (pin "112") (pinfunction "112_112") (pintype "passive"))
      (node (ref "EC1") (pin "48") (pinfunction "48_48") (pintype "passive"))
      (node (ref "EC1") (pin "84") (pinfunction "84_84") (pintype "passive"))
      (node (ref "EC1") (pin "98") (pinfunction "98_98") (pintype "passive"))
      (node (ref "EC2") (pin "158") (pinfunction "158_158") (pintype "passive"))
      (node (ref "EC2") (pin "180") (pinfunction "180_180") (pintype "passive"))
    )
    (net (code "214") (name "Net-(U1B-GPIO59)") (class "Default")
      (node (ref "R3") (pin "2") (pinfunction "2_2") (pintype "passive"))
      (node (ref "U1") (pin "M16") (pinfunction "GPIO59_M16") (pintype "bidirectional"))
    )
    (net (code "215") (name "Net-(U1B-GPIO61)") (class "Default")
      (node (ref "R4") (pin "2") (pinfunction "2_2") (pintype "passive"))
      (node (ref "U1") (pin "L16") (pinfunction "GPIO61_L16") (pintype "bidirectional"))
    )
    (net (code "216") (name "Net-(U1B-GPIO64)") (class "Default")
      (node (ref "R5") (pin "2") (pinfunction "2_2") (pintype "passive"))
      (node (ref "U1") (pin "L17") (pinfunction "GPIO64_L17") (pintype "bidirectional"))
    )
    (net (code "217") (name "Net-(U1B-GPIO66)") (class "Default")
      (node (ref "R6") (pin "2") (pinfunction "2_2") (pintype "passive"))
      (node (ref "U1") (pin "K17") (pinfunction "GPIO66_K17") (pintype "bidirectional"))
    )
    (net (code "218") (name "Net-(U1B-GPIO70)") (class "Default")
      (node (ref "R7") (pin "2") (pinfunction "2_2") (pintype "passive"))
      (node (ref "U1") (pin "A17") (pinfunction "GPIO70_A17") (pintype "bidirectional"))
    )
    (net (code "219") (name "Net-(U1B-GPIO72)") (class "Default")
      (node (ref "R8") (pin "2") (pinfunction "2_2") (pintype "passive"))
      (node (ref "U1") (pin "B16") (pinfunction "GPIO72_B16") (pintype "bidirectional"))
    )
    (net (code "220") (name "VDD_3V3") (class "Default")
      (node (ref "R1") (pin "2") (pinfunction "2_2") (pintype "passive"))
      (node (ref "R2") (pin "1") (pinfunction "1_1") (pintype "passive"))
    )
    (net (code "221") (name "unconnected-(EC1-Pad13)") (class "Default")
      (node (ref "EC1") (pin "13") (pinfunction "13_13") (pintype "passive+no_connect"))
    )
    (net (code "222") (name "unconnected-(EC1-Pad16)") (class "Default")
      (node (ref "EC1") (pin "16") (pinfunction "16_16") (pintype "passive+no_connect"))
    )
    (net (code "223") (name "unconnected-(EC1-Pad29)") (class "Default")
      (node (ref "EC1") (pin "29") (pinfunction "29_29") (pintype "passive+no_connect"))
    )
    (net (code "224") (name "unconnected-(EC1-Pad32)") (class "Default")
      (node (ref "EC1") (pin "32") (pinfunction "32_32") (pintype "passive+no_connect"))
    )
    (net (code "225") (name "unconnected-(EC1-Pad41)") (class "Default")
      (node (ref "EC1") (pin "41") (pinfunction "41_41") (pintype "passive+no_connect"))
    )
    (net (code "226") (name "unconnected-(EC1-Pad43)") (class "Default")
      (node (ref "EC1") (pin "43") (pinfunction "43_43") (pintype "passive+no_connect"))
    )
    (net (code "227") (name "unconnected-(EC1-Pad44)") (class "Default")
      (node (ref "EC1") (pin "44") (pinfunction "44_44") (pintype "passive+no_connect"))
    )
    (net (code "228") (name "unconnected-(EC1-Pad66)") (class "Default")
      (node (ref "EC1") (pin "66") (pinfunction "66_66") (pintype "passive+no_connect"))
    )
    (net (code "229") (name "unconnected-(EC1-Pad113)") (class "Default")
      (node (ref "EC1") (pin "113") (pinfunction "113_113") (pintype "passive+no_connect"))
    )
    (net (code "230") (name "unconnected-(EC1-Pad114)") (class "Default")
      (node (ref "EC1") (pin "114") (pinfunction "114_114") (pintype "passive+no_connect"))
    )
    (net (code "231") (name "unconnected-(EC1-Pad115)") (class "Default")
      (node (ref "EC1") (pin "115") (pinfunction "115_115") (pintype "passive+no_connect"))
    )
    (net (code "232") (name "unconnected-(EC1-Pad116)") (class "Default")
      (node (ref "EC1") (pin "116") (pinfunction "116_116") (pintype "passive+no_connect"))
    )
    (net (code "233") (name "unconnected-(EC1-Pad117)") (class "Default")
      (node (ref "EC1") (pin "117") (pinfunction "117_117") (pintype "passive+no_connect"))
    )
    (net (code "234") (name "unconnected-(EC2-Pad136)") (class "Default")
      (node (ref "EC2") (pin "136") (pinfunction "136_136") (pintype "passive+no_connect"))
    )
    (net (code "235") (name "unconnected-(EC2-Pad171)") (class "Default")
      (node (ref "EC2") (pin "171") (pinfunction "171_171") (pintype "passive+no_connect"))
    )
    (net (code "236") (name "unconnected-(EC2-Pad172)") (class "Default")
      (node (ref "EC2") (pin "172") (pinfunction "172_172") (pintype "passive+no_connect"))
    )
    (net (code "237") (name "unconnected-(EC2-Pad173)") (class "Default")
      (node (ref "EC2") (pin "173") (pinfunction "173_173") (pintype "passive+no_connect"))
    )
    (net (code "238") (name "unconnected-(EC2-Pad174)") (class "Default")
      (node (ref "EC2") (pin "174") (pinfunction "174_174") (pintype "passive+no_connect"))
    )
    (net (code "239") (name "unconnected-(EC2-Pad175)") (class "Default")
      (node (ref "EC2") (pin "175") (pinfunction "175_175") (pintype "passive+no_connect"))
    )
    (net (code "240") (name "unconnected-(EC2-Pad176)") (class "Default")
      (node (ref "EC2") (pin "176") (pinfunction "176_176") (pintype "passive+no_connect"))
    )
    (net (code "241") (name "unconnected-(EC2-Pad177)") (class "Default")
      (node (ref "EC2") (pin "177") (pinfunction "177_177") (pintype "passive+no_connect"))
    )
  )
)
